# FTDI_FT232R_USB_To_UART.net
KiCad netlist of a schematic drawn in Altium Designer
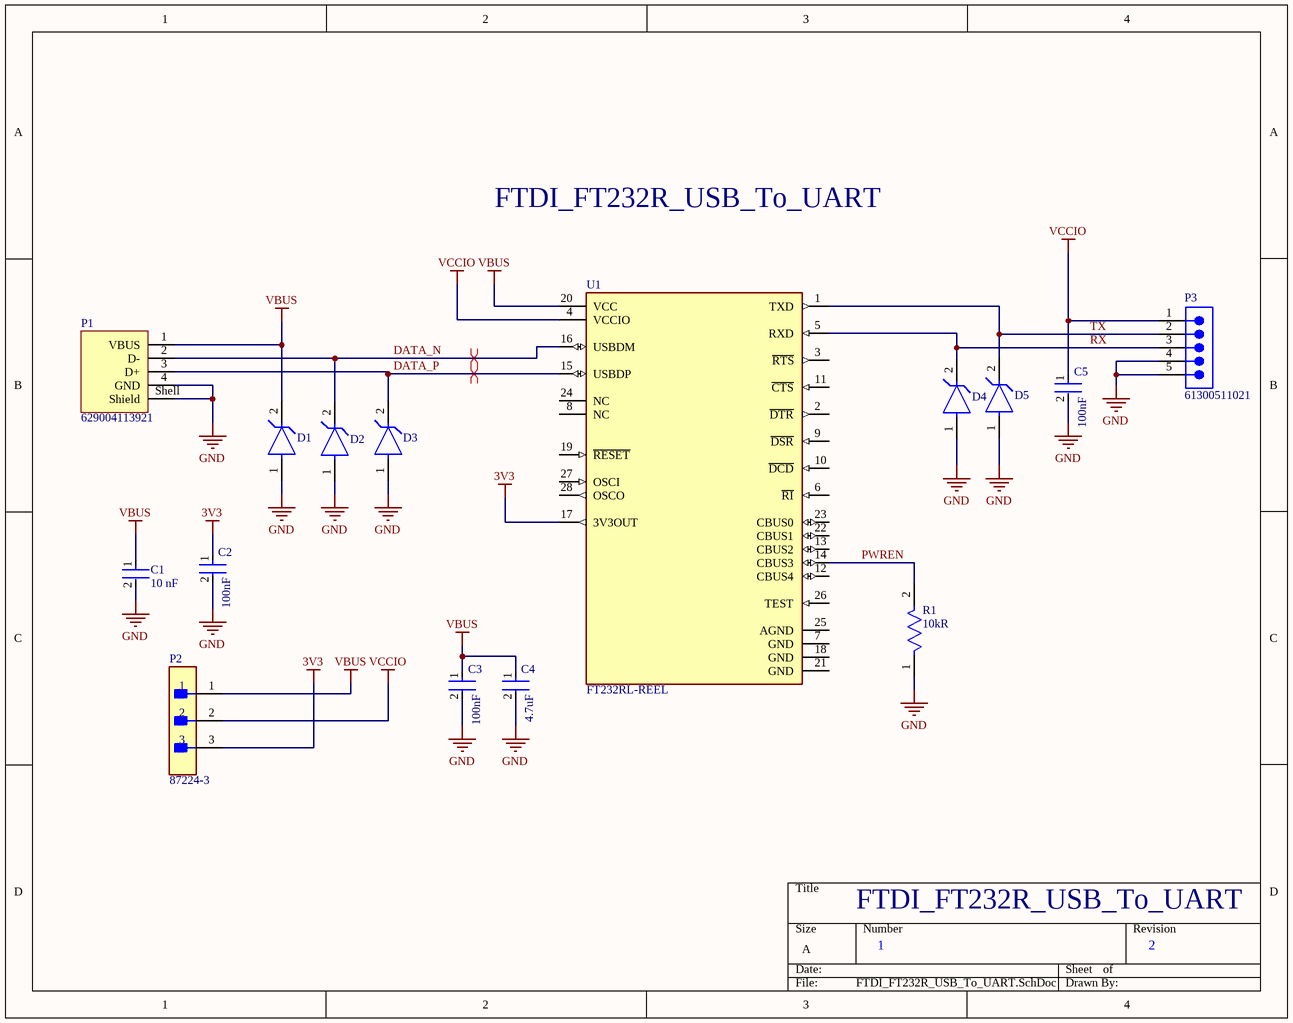
[diagram p0: FTDI_FT232R_USB_To_UART.SchDoc]

(export (version "E")
  (design (tool "Eeschema 10.0.6"))
  (components
    (comp (ref "C1")
      (value "CC0402KPX7R7BB103")
      (footprint "FP-CC0402-MFG")
      (description "CC0402 10 nF X7R 10.00% 16 V")
      (fields
        (field (name "CAPACITANCE") "10 nF")
        (field (name "TOLERANCE") "0.1")
        (field (name "OCTOPART") "https://octopart.com/cc0402kpx7r7bb103-yageo-12885102")
      )
      (libsource (lib "Altium Content Vault") (part "11868f565c42a9108669ba33697ecf6"))
    )
    (comp (ref "C2")
      (value "C1005X7R1C104K050BC")
      (footprint "FP-C1005-050-0_05-MFG")
      (description "Multilayer Ceramic Capacitors 100nF ±10% 16V X7R SMD 0402")
      (fields
        (field (name "VOLTAGE") "16V")
        (field (name "CAPACITANCE") "100nF")
        (field (name "TOLERANCE") "10%")
      )
      (libsource (lib "Altium Content Vault") (part "b4654b650e69147ec39a6b967a45e02"))
    )
    (comp (ref "C3")
      (value "C1005X7R1C104K050BC")
      (footprint "FP-C1005-050-0_05-MFG")
      (description "Multilayer Ceramic Capacitors 100nF ±10% 16V X7R SMD 0402")
      (fields
        (field (name "VOLTAGE") "16V")
        (field (name "CAPACITANCE") "100nF")
        (field (name "TOLERANCE") "10%")
      )
      (libsource (lib "Altium Content Vault") (part "b4654b650e69147ec39a6b967a45e02"))
    )
    (comp (ref "C4")
      (value "GRM155R61A475MEAAD")
      (footprint "FP-GRM155-0_15-MFG")
      (description "Chip Multilayer Ceramic Capacitors for General Purpose, 0402, 4.7uF, X5R, 15%, 20%, 10V")
      (fields (field (name "CAPACITANCE") "4.7uF") (field (name "TOLERANCE") "20%"))
      (libsource (lib "Altium Content Vault") (part "b4654b650e69147ec39a6b967a45e02"))
    )
    (comp (ref "C5")
      (value "C1005X7R1C104K050BC")
      (footprint "FP-C1005-050-0_05-MFG")
      (description "Multilayer Ceramic Capacitors 100nF ±10% 16V X7R SMD 0402")
      (fields
        (field (name "VOLTAGE") "16V")
        (field (name "CAPACITANCE") "100nF")
        (field (name "TOLERANCE") "10%")
      )
      (libsource (lib "Altium Content Vault") (part "b4654b650e69147ec39a6b967a45e02"))
    )
    (comp (ref "D1")
      (value "UCLAMP3601P.TNT")
      (footprint "FP-SLP1006P2-MFG")
      (description "TVS DIODE 33VWM 60VC SLP1006P2")
      (libsource (lib "Altium Content Vault") (part "3fba79ac723ca0a4e69928609483429"))
    )
    (comp (ref "D2")
      (value "UCLAMP3601P.TNT")
      (footprint "FP-SLP1006P2-MFG")
      (description "TVS DIODE 33VWM 60VC SLP1006P2")
      (libsource (lib "Altium Content Vault") (part "3fba79ac723ca0a4e69928609483429"))
    )
    (comp (ref "D3")
      (value "UCLAMP3601P.TNT")
      (footprint "FP-SLP1006P2-MFG")
      (description "TVS DIODE 33VWM 60VC SLP1006P2")
      (libsource (lib "Altium Content Vault") (part "3fba79ac723ca0a4e69928609483429"))
    )
    (comp (ref "D4")
      (value "UCLAMP3601P.TNT")
      (footprint "FP-SLP1006P2-MFG")
      (description "TVS DIODE 33VWM 60VC SLP1006P2")
      (libsource (lib "Altium Content Vault") (part "3fba79ac723ca0a4e69928609483429"))
    )
    (comp (ref "D5")
      (value "UCLAMP3601P.TNT")
      (footprint "FP-SLP1006P2-MFG")
      (description "TVS DIODE 33VWM 60VC SLP1006P2")
      (libsource (lib "Altium Content Vault") (part "3fba79ac723ca0a4e69928609483429"))
    )
    (comp (ref "P1")
      (value "629004113921")
      (footprint "629004113921")
      (libsource (lib "Altium Content Vault") (part "USB 2.0_Type A_Plug_1 Port"))
    )
    (comp (ref "P2")
      (value "87224-3")
      (footprint "FP-87224-3-MFG")
      (description "CONN HEADER VERT 3POS 2.54MM")
      (libsource (lib "Altium Content Vault") (part "0d3f023dd272f625e17a2be33dea85f"))
    )
    (comp (ref "P3")
      (value "61300511021")
      (footprint "61300511021")
      (libsource (lib "Altium Content Vault") (part "Header_Male_1R_05P"))
    )
    (comp (ref "R1")
      (value "CRG0402F10K")
      (footprint "FP-CRG0402-IPC_B")
      (description "RES SMD 10K OHM 1% 1/16W 0402")
      (fields (field (name "RESISTANCE") "10kR") (field (name "TOLERANCE") "1%"))
      (libsource (lib "Altium Content Vault") (part "1029c3af85768c4190bb7ad29bc67b5"))
    )
    (comp (ref "U1")
      (value "FT232RL-REEL")
      (footprint "FP-SSOP-28-MFG")
      (description "IC USB FS SERIAL UART 28-SSOP")
      (fields (field (name "VOLTAGE") "5V"))
      (libsource (lib "Altium Content Vault") (part "fa727c664f4d88ca0f1b580aa0dd901"))
    )
  )
  (nets
    (net (code "1") (name "/DATA_N") (class "Default")
      (node (ref "D2") (pin "2") (pinfunction "C_2") (pintype "passive"))
      (node (ref "P1") (pin "2") (pinfunction "D-_2") (pintype "passive"))
      (node (ref "U1") (pin "16") (pinfunction "USBDM_16") (pintype "bidirectional"))
    )
    (net (code "2") (name "/DATA_P") (class "Default")
      (node (ref "D3") (pin "2") (pinfunction "C_2") (pintype "passive"))
      (node (ref "P1") (pin "3") (pinfunction "D+_3") (pintype "passive"))
      (node (ref "U1") (pin "15") (pinfunction "USBDP_15") (pintype "bidirectional"))
    )
    (net (code "3") (name "/PWREN") (class "Default")
      (node (ref "R1") (pin "2") (pinfunction "2_2") (pintype "passive"))
      (node (ref "U1") (pin "14") (pinfunction "CBUS3_14") (pintype "bidirectional"))
    )
    (net (code "4") (name "/RX") (class "Default")
      (node (ref "D4") (pin "2") (pinfunction "C_2") (pintype "passive"))
      (node (ref "P3") (pin "3") (pinfunction "3_3") (pintype "passive"))
      (node (ref "U1") (pin "5") (pinfunction "RXD_5") (pintype "input"))
    )
    (net (code "5") (name "/TX") (class "Default")
      (node (ref "D5") (pin "2") (pinfunction "C_2") (pintype "passive"))
      (node (ref "P3") (pin "2") (pinfunction "2_2") (pintype "passive"))
      (node (ref "U1") (pin "1") (pinfunction "TXD_1") (pintype "output"))
    )
    (net (code "6") (name "3V3") (class "Default")
      (node (ref "C2") (pin "1") (pinfunction "1_1") (pintype "passive"))
      (node (ref "P2") (pin "3") (pinfunction "3_3") (pintype "passive"))
      (node (ref "U1") (pin "17") (pinfunction "3V3OUT_17") (pintype "output"))
    )
    (net (code "7") (name "GND") (class "Default")
      (node (ref "C1") (pin "2") (pinfunction "2_2") (pintype "passive"))
      (node (ref "C2") (pin "2") (pinfunction "2_2") (pintype "passive"))
      (node (ref "C3") (pin "2") (pinfunction "2_2") (pintype "passive"))
      (node (ref "C4") (pin "2") (pinfunction "2_2") (pintype "passive"))
      (node (ref "C5") (pin "2") (pinfunction "2_2") (pintype "passive"))
      (node (ref "D1") (pin "1") (pinfunction "A_1") (pintype "passive"))
      (node (ref "D2") (pin "1") (pinfunction "A_1") (pintype "passive"))
      (node (ref "D3") (pin "1") (pinfunction "A_1") (pintype "passive"))
      (node (ref "D4") (pin "1") (pinfunction "A_1") (pintype "passive"))
      (node (ref "D5") (pin "1") (pinfunction "A_1") (pintype "passive"))
      (node (ref "P1") (pin "4") (pinfunction "GND_4") (pintype "passive"))
      (node (ref "P1") (pin "Shell") (pinfunction "Shield_Shell") (pintype "passive"))
      (node (ref "P3") (pin "4") (pinfunction "4_4") (pintype "passive"))
      (node (ref "P3") (pin "5") (pinfunction "5_5") (pintype "passive"))
      (node (ref "R1") (pin "1") (pinfunction "1_1") (pintype "passive"))
    )
    (net (code "8") (name "VBUS") (class "Default")
      (node (ref "C1") (pin "1") (pinfunction "1_1") (pintype "passive"))
      (node (ref "C3") (pin "1") (pinfunction "1_1") (pintype "passive"))
      (node (ref "C4") (pin "1") (pinfunction "1_1") (pintype "passive"))
      (node (ref "D1") (pin "2") (pinfunction "C_2") (pintype "passive"))
      (node (ref "P1") (pin "1") (pinfunction "VBUS_1") (pintype "passive"))
      (node (ref "P2") (pin "1") (pinfunction "1_1") (pintype "passive"))
      (node (ref "U1") (pin "20") (pinfunction "VCC_20") (pintype "power_in"))
    )
    (net (code "9") (name "VCCIO") (class "Default")
      (node (ref "C5") (pin "1") (pinfunction "1_1") (pintype "passive"))
      (node (ref "P2") (pin "2") (pinfunction "2_2") (pintype "passive"))
      (node (ref "P3") (pin "1") (pinfunction "1_1") (pintype "passive"))
      (node (ref "U1") (pin "4") (pinfunction "VCCIO_4") (pintype "power_in"))
    )
    (net (code "10") (name "unconnected-(U1-AGND-Pad25)") (class "Default")
      (node (ref "U1") (pin "25") (pinfunction "AGND_25") (pintype "power_in"))
    )
    (net (code "11") (name "unconnected-(U1-CBUS0-Pad23)") (class "Default")
      (node (ref "U1") (pin "23") (pinfunction "CBUS0_23") (pintype "bidirectional"))
    )
    (net (code "12") (name "unconnected-(U1-CBUS1-Pad22)") (class "Default")
      (node (ref "U1") (pin "22") (pinfunction "CBUS1_22") (pintype "bidirectional"))
    )
    (net (code "13") (name "unconnected-(U1-CBUS2-Pad13)") (class "Default")
      (node (ref "U1") (pin "13") (pinfunction "CBUS2_13") (pintype "bidirectional"))
    )
    (net (code "14") (name "unconnected-(U1-CBUS4-Pad12)") (class "Default")
      (node (ref "U1") (pin "12") (pinfunction "CBUS4_12") (pintype "bidirectional"))
    )
    (net (code "15") (name "unconnected-(U1-GND-Pad7)") (class "Default")
      (node (ref "U1") (pin "7") (pinfunction "GND_7") (pintype "power_in"))
    )
    (net (code "16") (name "unconnected-(U1-GND-Pad18)") (class "Default")
      (node (ref "U1") (pin "18") (pinfunction "GND_18") (pintype "power_in"))
    )
    (net (code "17") (name "unconnected-(U1-GND-Pad21)") (class "Default")
      (node (ref "U1") (pin "21") (pinfunction "GND_21") (pintype "power_in"))
    )
    (net (code "18") (name "unconnected-(U1-NC-Pad8)") (class "Default")
      (node (ref "U1") (pin "8") (pinfunction "NC_8") (pintype "passive"))
    )
    (net (code "19") (name "unconnected-(U1-NC-Pad24)") (class "Default")
      (node (ref "U1") (pin "24") (pinfunction "NC_24") (pintype "passive"))
    )
    (net (code "20") (name "unconnected-(U1-OSCI-Pad27)") (class "Default")
      (node (ref "U1") (pin "27") (pinfunction "OSCI_27") (pintype "input"))
    )
    (net (code "21") (name "unconnected-(U1-OSCO-Pad28)") (class "Default")
      (node (ref "U1") (pin "28") (pinfunction "OSCO_28") (pintype "output"))
    )
    (net (code "22") (name "unconnected-(U1-TEST-Pad26)") (class "Default")
      (node (ref "U1") (pin "26") (pinfunction "TEST_26") (pintype "input"))
    )
    (net (code "23") (name "unconnected-(U1-~{CTS}-Pad11)") (class "Default")
      (node (ref "U1") (pin "11") (pinfunction "~{CTS}_11") (pintype "input"))
    )
    (net (code "24") (name "unconnected-(U1-~{DCD}-Pad10)") (class "Default")
      (node (ref "U1") (pin "10") (pinfunction "~{DCD}_10") (pintype "input"))
    )
    (net (code "25") (name "unconnected-(U1-~{DSR}-Pad9)") (class "Default")
      (node (ref "U1") (pin "9") (pinfunction "~{DSR}_9") (pintype "input"))
    )
    (net (code "26") (name "unconnected-(U1-~{DTR}-Pad2)") (class "Default")
      (node (ref "U1") (pin "2") (pinfunction "~{DTR}_2") (pintype "output"))
    )
    (net (code "27") (name "unconnected-(U1-~{RESET}-Pad19)") (class "Default")
      (node (ref "U1") (pin "19") (pinfunction "~{RESET}_19") (pintype "input"))
    )
    (net (code "28") (name "unconnected-(U1-~{RI}-Pad6)") (class "Default")
      (node (ref "U1") (pin "6") (pinfunction "~{RI}_6") (pintype "input"))
    )
    (net (code "29") (name "unconnected-(U1-~{RTS}-Pad3)") (class "Default")
      (node (ref "U1") (pin "3") (pinfunction "~{RTS}_3") (pintype "output"))
    )
  )
)
